# MTCH9010_Sensors.net
KiCad netlist of a schematic drawn in Altium Designer
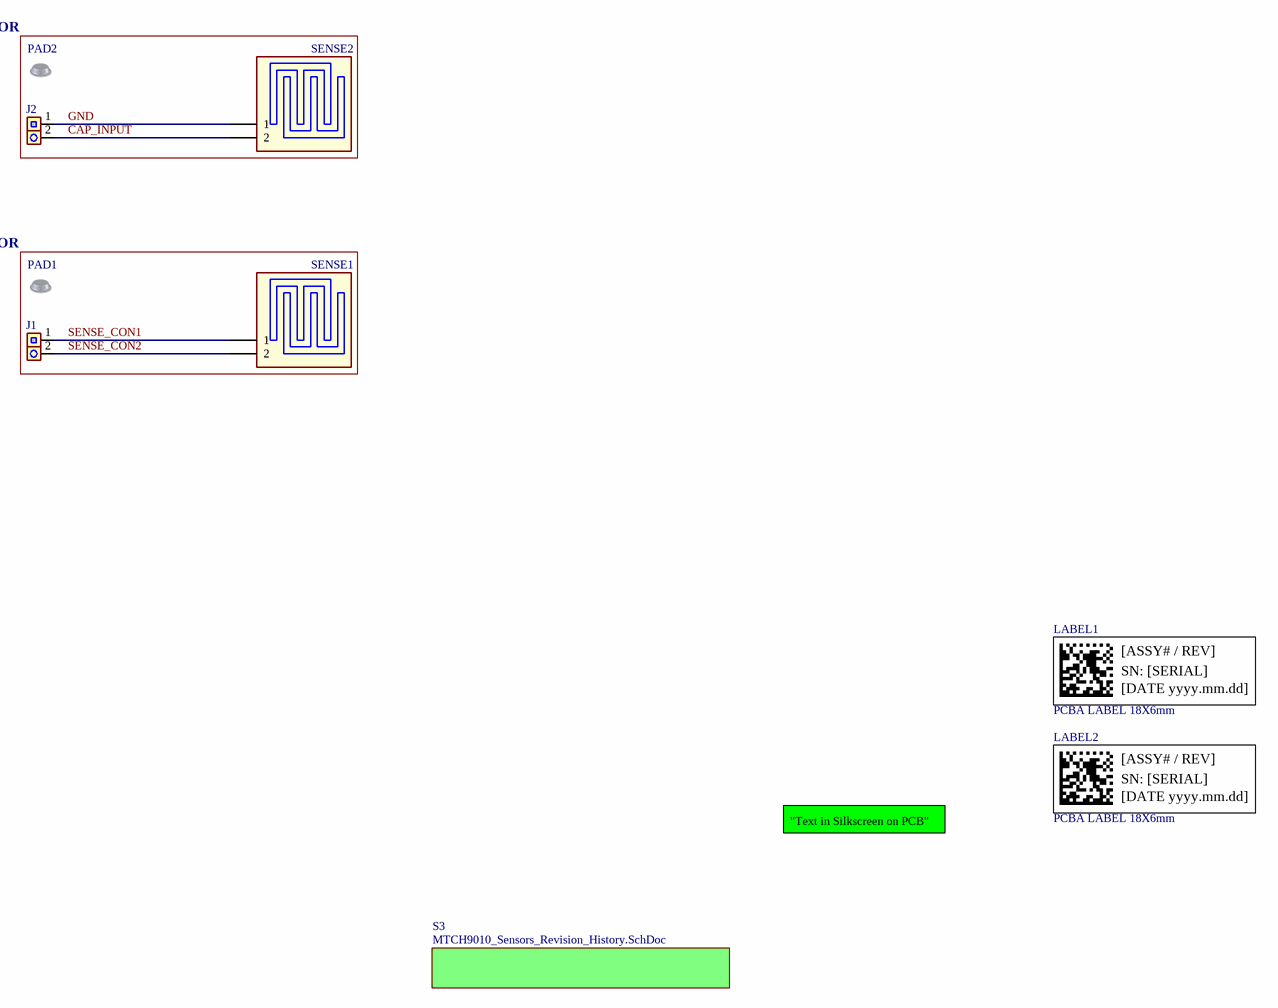
[diagram p0: MTCH9010_Sensors.SchDoc]

(export (version "E")
  (design (tool "Eeschema 10.0.6"))
  (components
    (comp (ref "J1")
      (value "Header 1x2")
      (footprint "HDR_M_2.54_1X2_U_TH-PIP_RA_WCON_1125-1102S0R140CR01")
      (fields (field (name "VOLTAGE") "1kV"))
      (libsource (lib "MCHP-CDB") (part "Header 1x2"))
    )
    (comp (ref "J2")
      (value "Header 1x2")
      (footprint "HDR_M_2.54_1X2_U_TH-PIP_RA_WCON_1125-1102S0R140CR01")
      (fields (field (name "VOLTAGE") "1kV"))
      (libsource (lib "MCHP-CDB") (part "Header 1x2"))
    )
    (comp (ref "LABEL1")
      (value "PCBA LABEL 18X6mm")
      (footprint "08-10015")
      (fields (field (name "Comment") "08-10015"))
      (libsource (lib "MCHP-CDB") (part "08-10015"))
    )
    (comp (ref "LABEL2")
      (value "PCBA LABEL 18X6mm")
      (footprint "08-10015")
      (fields (field (name "Comment") "08-10015"))
      (libsource (lib "MCHP-CDB") (part "08-10015"))
    )
    (comp (ref "PAD1")
      (value "Rubber Pad Cylindrical Taper")
      (footprint "BUMP_BUMPERSPECIALTIES_BS06GR10X20RP_CYLINDRICAL_BLACK_D12.7H6.35")
      (libsource (lib "MCHP-CDB") (part "Rubber Pad Cylindrical Taper"))
    )
    (comp (ref "PAD2")
      (value "Rubber Pad Cylindrical Taper")
      (footprint "BUMP_BUMPERSPECIALTIES_BS06GR10X20RP_CYLINDRICAL_BLACK_D12.7H6.35")
      (libsource (lib "MCHP-CDB") (part "Rubber Pad Cylindrical Taper"))
    )
    (comp (ref "SENSE1")
      (value "Liquid_Sensor")
      (footprint "Con_20x20x0.5x0.5")
      (libsource (lib "Liquid_Sensor") (part "Liquid_Sensor"))
    )
    (comp (ref "SENSE2")
      (value "Liquid_Sensor")
      (footprint "Cap_20x20x1x0.5:Cap_20x20x1x0.5")
      (libsource (lib "Liquid_Sensor") (part "Liquid_Sensor"))
    )
  )
  (nets
    (net (code "1") (name "/CAP_INPUT") (class "Default")
      (node (ref "J2") (pin "2") (pinfunction "2_2") (pintype "passive"))
      (node (ref "SENSE2") (pin "2") (pinfunction "2_2") (pintype "passive"))
    )
    (net (code "2") (name "/GND") (class "Default")
      (node (ref "J2") (pin "1") (pinfunction "1_1") (pintype "passive"))
      (node (ref "SENSE2") (pin "1") (pinfunction "1_1") (pintype "passive"))
    )
    (net (code "3") (name "/SENSE_CON1") (class "Default")
      (node (ref "J1") (pin "1") (pinfunction "1_1") (pintype "passive"))
      (node (ref "SENSE1") (pin "1") (pinfunction "1_1") (pintype "passive"))
    )
    (net (code "4") (name "/SENSE_CON2") (class "Default")
      (node (ref "J1") (pin "2") (pinfunction "2_2") (pintype "passive"))
      (node (ref "SENSE1") (pin "2") (pinfunction "2_2") (pintype "passive"))
    )
  )
)
